# Adafruit_PiTFT_3_2in.net
KiCad netlist of a schematic drawn in EAGLE
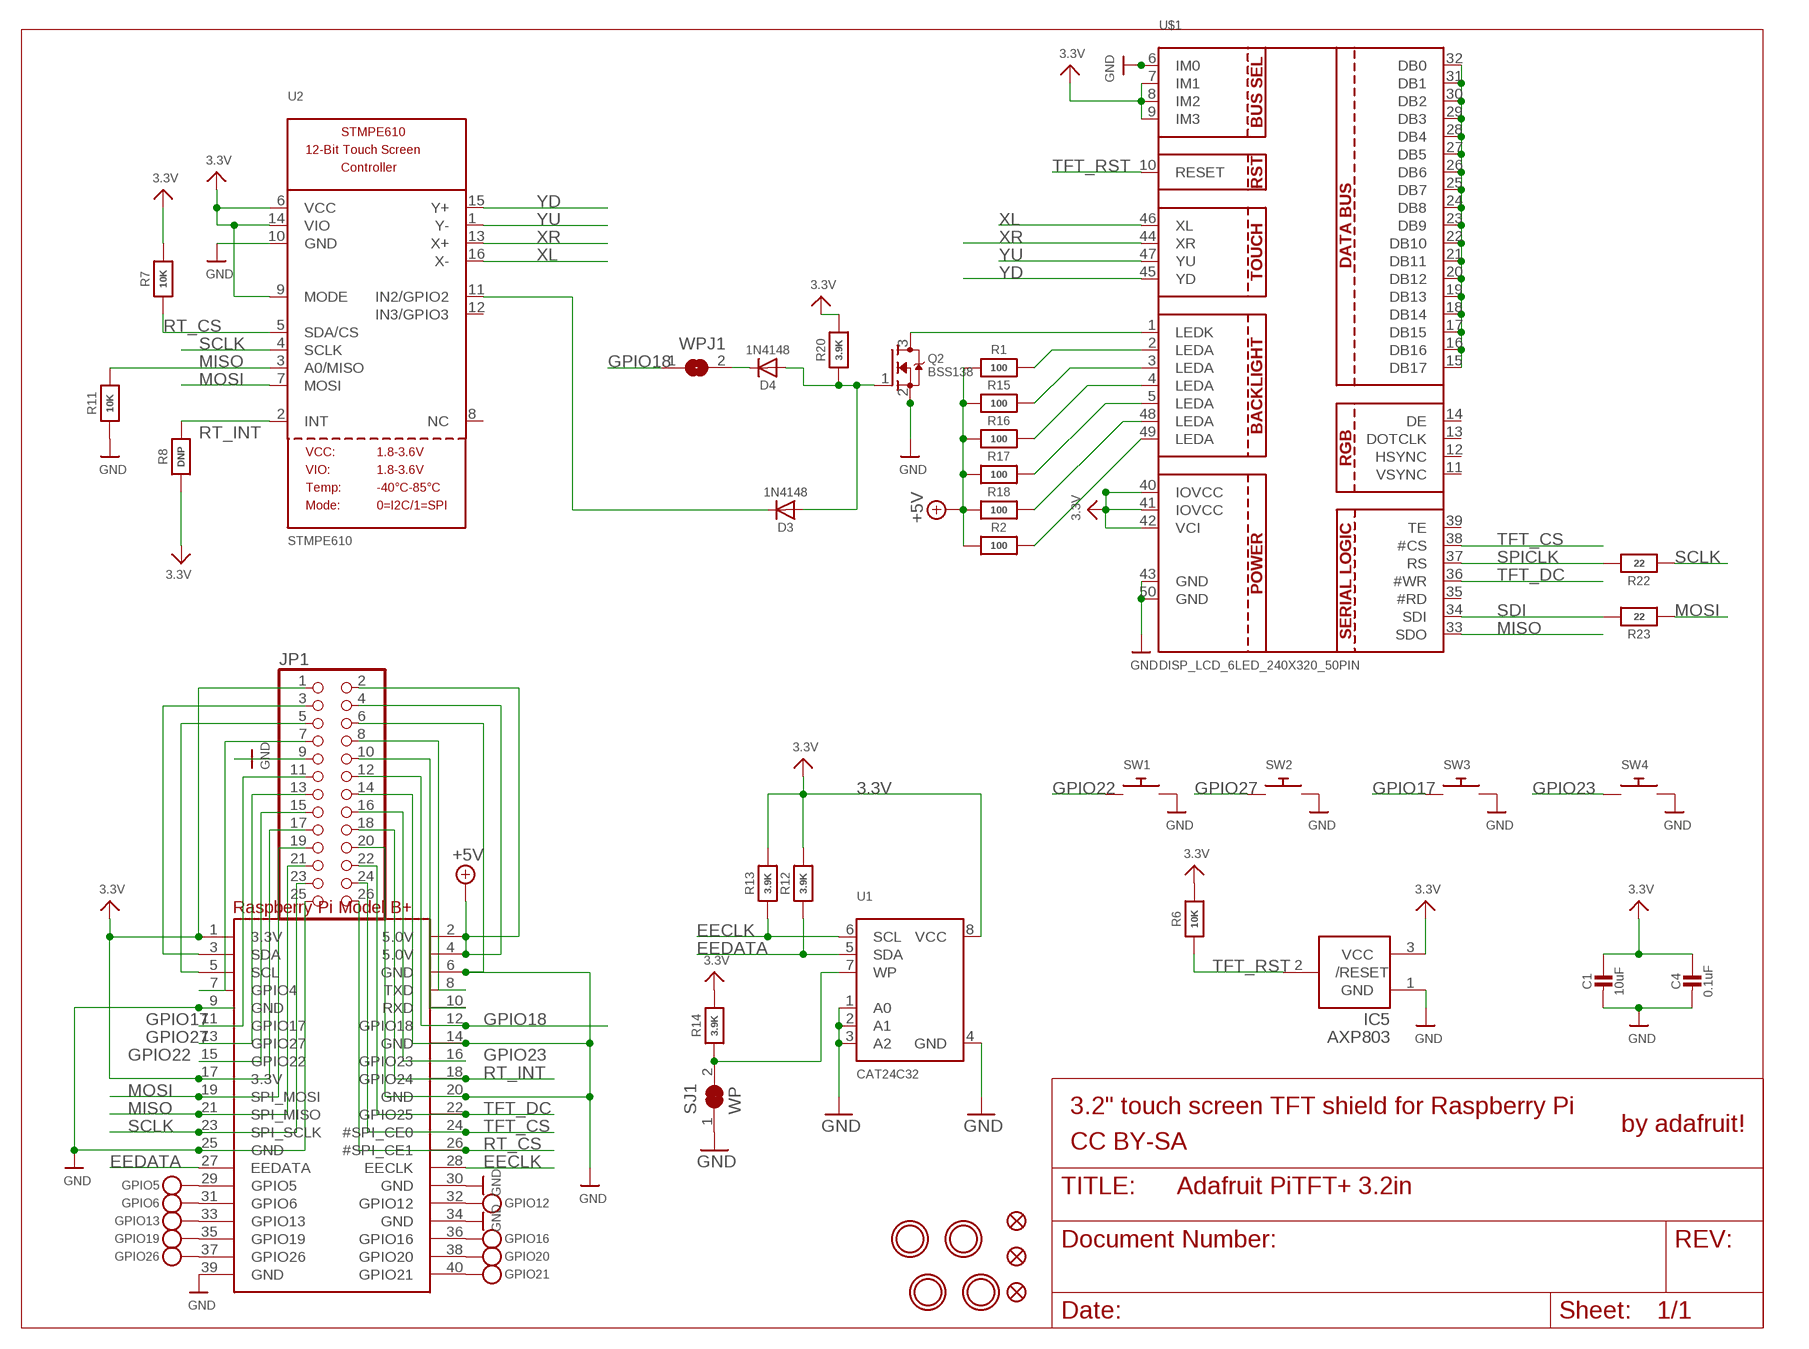
[diagram p0: schematic, sheet 1]

(export (version "E")
  (design (tool "Eeschema 10.0.6"))
  (components
    (comp (ref "C1")
      (value "10uF")
      (footprint "eagle-import:0805-NO")
      (libsource (lib "eagle-import") (part "CAP_CERAMIC0805-NOOUTLINE"))
    )
    (comp (ref "C4")
      (value "0.1uF")
      (footprint "eagle-import:0805-NO")
      (libsource (lib "eagle-import") (part "CAP_CERAMIC0805-NOOUTLINE"))
    )
    (comp (ref "D3")
      (value "1N4148")
      (footprint "eagle-import:SOD-323")
      (libsource (lib "eagle-import") (part "DIODESOD-323"))
    )
    (comp (ref "D4")
      (value "1N4148")
      (footprint "eagle-import:SOD-323")
      (libsource (lib "eagle-import") (part "DIODESOD-323"))
    )
    (comp (ref "GPIO5")
      (value "TESTPOINT1.5X2.0MM_NOCREAM")
      (footprint "eagle-import:PAD-1.5X2.0")
      (libsource (lib "eagle-import") (part "TESTPOINT1.5X2.0MM_NOCREAM"))
    )
    (comp (ref "GPIO6")
      (value "TESTPOINT1.5X2.0MM_NOCREAM")
      (footprint "eagle-import:PAD-1.5X2.0")
      (libsource (lib "eagle-import") (part "TESTPOINT1.5X2.0MM_NOCREAM"))
    )
    (comp (ref "GPIO12")
      (value "TESTPOINT1.5X2.0MM_NOCREAM")
      (footprint "eagle-import:PAD-1.5X2.0")
      (libsource (lib "eagle-import") (part "TESTPOINT1.5X2.0MM_NOCREAM"))
    )
    (comp (ref "GPIO13")
      (value "TESTPOINT1.5X2.0MM_NOCREAM")
      (footprint "eagle-import:PAD-1.5X2.0")
      (libsource (lib "eagle-import") (part "TESTPOINT1.5X2.0MM_NOCREAM"))
    )
    (comp (ref "GPIO16")
      (value "TESTPOINT1.5X2.0MM_NOCREAM")
      (footprint "eagle-import:PAD-1.5X2.0")
      (libsource (lib "eagle-import") (part "TESTPOINT1.5X2.0MM_NOCREAM"))
    )
    (comp (ref "GPIO19")
      (value "TESTPOINT1.5X2.0MM_NOCREAM")
      (footprint "eagle-import:PAD-1.5X2.0")
      (libsource (lib "eagle-import") (part "TESTPOINT1.5X2.0MM_NOCREAM"))
    )
    (comp (ref "GPIO20")
      (value "TESTPOINT1.5X2.0MM_NOCREAM")
      (footprint "eagle-import:PAD-1.5X2.0")
      (libsource (lib "eagle-import") (part "TESTPOINT1.5X2.0MM_NOCREAM"))
    )
    (comp (ref "GPIO21")
      (value "TESTPOINT1.5X2.0MM_NOCREAM")
      (footprint "eagle-import:PAD-1.5X2.0")
      (libsource (lib "eagle-import") (part "TESTPOINT1.5X2.0MM_NOCREAM"))
    )
    (comp (ref "GPIO26")
      (value "TESTPOINT1.5X2.0MM_NOCREAM")
      (footprint "eagle-import:PAD-1.5X2.0")
      (libsource (lib "eagle-import") (part "TESTPOINT1.5X2.0MM_NOCREAM"))
    )
    (comp (ref "IC5")
      (value "AXP803")
      (footprint "eagle-import:SOT23")
      (libsource (lib "eagle-import") (part "AXP083-SAG"))
    )
    (comp (ref "JP1")
      (value "HEADER-2X13-SMT")
      (footprint "eagle-import:2X13_SMT_MALE")
      (libsource (lib "eagle-import") (part "HEADER-2X13-SMT"))
    )
    (comp (ref "Q2")
      (value "BSS138")
      (footprint "eagle-import:SOT23-WIDE")
      (libsource (lib "eagle-import") (part "MOSFET-NWIDE"))
    )
    (comp (ref "R1")
      (value "100")
      (footprint "eagle-import:0805-NO")
      (libsource (lib "eagle-import") (part "RESISTOR0805_NOOUTLINE"))
    )
    (comp (ref "R2")
      (value "100")
      (footprint "eagle-import:0805-NO")
      (libsource (lib "eagle-import") (part "RESISTOR0805_NOOUTLINE"))
    )
    (comp (ref "R6")
      (value "10K")
      (footprint "eagle-import:0805-NO")
      (libsource (lib "eagle-import") (part "RESISTOR0805_NOOUTLINE"))
    )
    (comp (ref "R7")
      (value "10K")
      (footprint "eagle-import:0805-NO")
      (libsource (lib "eagle-import") (part "RESISTOR0805_NOOUTLINE"))
    )
    (comp (ref "R8")
      (value "DNP")
      (footprint "eagle-import:0805-NO")
      (libsource (lib "eagle-import") (part "RESISTOR0805_NOOUTLINE"))
    )
    (comp (ref "R11")
      (value "10K")
      (footprint "eagle-import:0805-NO")
      (libsource (lib "eagle-import") (part "RESISTOR0805_NOOUTLINE"))
    )
    (comp (ref "R12")
      (value "3.9K")
      (footprint "eagle-import:0805-NO")
      (libsource (lib "eagle-import") (part "RESISTOR0805_NOOUTLINE"))
    )
    (comp (ref "R13")
      (value "3.9K")
      (footprint "eagle-import:0805-NO")
      (libsource (lib "eagle-import") (part "RESISTOR0805_NOOUTLINE"))
    )
    (comp (ref "R14")
      (value "3.9K")
      (footprint "eagle-import:0805-NO")
      (libsource (lib "eagle-import") (part "RESISTOR0805_NOOUTLINE"))
    )
    (comp (ref "R15")
      (value "100")
      (footprint "eagle-import:0805-NO")
      (libsource (lib "eagle-import") (part "RESISTOR0805_NOOUTLINE"))
    )
    (comp (ref "R16")
      (value "100")
      (footprint "eagle-import:0805-NO")
      (libsource (lib "eagle-import") (part "RESISTOR0805_NOOUTLINE"))
    )
    (comp (ref "R17")
      (value "100")
      (footprint "eagle-import:0805-NO")
      (libsource (lib "eagle-import") (part "RESISTOR0805_NOOUTLINE"))
    )
    (comp (ref "R18")
      (value "100")
      (footprint "eagle-import:0805-NO")
      (libsource (lib "eagle-import") (part "RESISTOR0805_NOOUTLINE"))
    )
    (comp (ref "R20")
      (value "3.9K")
      (footprint "eagle-import:0805-NO")
      (libsource (lib "eagle-import") (part "RESISTOR0805_NOOUTLINE"))
    )
    (comp (ref "R22")
      (value "22")
      (footprint "eagle-import:0805-NO")
      (libsource (lib "eagle-import") (part "RESISTOR0805_NOOUTLINE"))
    )
    (comp (ref "R23")
      (value "22")
      (footprint "eagle-import:_0805MP")
      (libsource (lib "eagle-import") (part "RESISTOR_0805MP"))
    )
    (comp (ref "RPI1")
      (value "RASPBERRYPI_BPLUS_SMT")
      (footprint "eagle-import:RASPBERRYPI_BPLUS_SHIELD_SMT")
      (libsource (lib "eagle-import") (part "RASPBERRYPI_BPLUS_SMT"))
    )
    (comp (ref "SJ1")
      (value "WP")
      (footprint "eagle-import:SOLDERJUMPER_CLOSEDWIRE")
      (libsource (lib "eagle-import") (part "SOLDERJUMPER_CLOSED"))
    )
    (comp (ref "SW1")
      (value "SWITCH_PUSHBUTTONEVQ-PE")
      (footprint "eagle-import:TACT_PANA-EVQ")
      (libsource (lib "eagle-import") (part "SWITCH_PUSHBUTTONEVQ-PE"))
    )
    (comp (ref "SW2")
      (value "SWITCH_PUSHBUTTONEVQ-PE")
      (footprint "eagle-import:TACT_PANA-EVQ")
      (libsource (lib "eagle-import") (part "SWITCH_PUSHBUTTONEVQ-PE"))
    )
    (comp (ref "SW3")
      (value "SWITCH_PUSHBUTTONEVQ-PE")
      (footprint "eagle-import:TACT_PANA-EVQ")
      (libsource (lib "eagle-import") (part "SWITCH_PUSHBUTTONEVQ-PE"))
    )
    (comp (ref "SW4")
      (value "SWITCH_PUSHBUTTONEVQ-PE")
      (footprint "eagle-import:TACT_PANA-EVQ")
      (libsource (lib "eagle-import") (part "SWITCH_PUSHBUTTONEVQ-PE"))
    )
    (comp (ref "U$1")
      (value "DISP_LCD_6LED_240X320_50PIN")
      (footprint "eagle-import:TFT_3.2IN_240X320_50PIN")
      (libsource (lib "eagle-import") (part "DISP_LCD_6LED_240X320_50PIN"))
    )
    (comp (ref "U$10")
      (value "FIDUCIAL\"\"")
      (footprint "eagle-import:FIDUCIAL_1MM")
      (libsource (lib "eagle-import") (part "FIDUCIAL{dblquote}{dblquote}"))
    )
    (comp (ref "U$11")
      (value "FIDUCIAL\"\"")
      (footprint "eagle-import:FIDUCIAL_1MM")
      (libsource (lib "eagle-import") (part "FIDUCIAL{dblquote}{dblquote}"))
    )
    (comp (ref "U$15")
      (value "MOUNTINGHOLE2.5_THICK")
      (footprint "eagle-import:MOUNTINGHOLE_2.5_PLATED_THICK")
      (libsource (lib "eagle-import") (part "MOUNTINGHOLE2.5_THICK"))
    )
    (comp (ref "U$16")
      (value "MOUNTINGHOLE2.5_THICK")
      (footprint "eagle-import:MOUNTINGHOLE_2.5_PLATED_THICK")
      (libsource (lib "eagle-import") (part "MOUNTINGHOLE2.5_THICK"))
    )
    (comp (ref "U$17")
      (value "MOUNTINGHOLE2.5_THICK")
      (footprint "eagle-import:MOUNTINGHOLE_2.5_PLATED_THICK")
      (fields (field (name "BOM") "EXCLUDE"))
      (libsource (lib "eagle-import") (part "MOUNTINGHOLE2.5_THICK"))
    )
    (comp (ref "U$18")
      (value "FIDUCIAL\"\"")
      (footprint "eagle-import:FIDUCIAL_1MM")
      (libsource (lib "eagle-import") (part "FIDUCIAL{dblquote}{dblquote}"))
    )
    (comp (ref "U$20")
      (value "MOUNTINGHOLE2.5_THICK")
      (footprint "eagle-import:MOUNTINGHOLE_2.5_PLATED_THICK")
      (fields (field (name "BOM") "EXCLUDE"))
      (libsource (lib "eagle-import") (part "MOUNTINGHOLE2.5_THICK"))
    )
    (comp (ref "U1")
      (value "CAT24C32")
      (footprint "eagle-import:SOIC8_150MIL")
      (libsource (lib "eagle-import") (part "EEPROM_I2C_SOIC8_GENERIC"))
    )
    (comp (ref "U2")
      (value "STMPE610")
      (footprint "eagle-import:QFN16_3MM")
      (libsource (lib "eagle-import") (part "STMPE610"))
    )
    (comp (ref "WPJ1")
      (value "SOLDERJUMPERCLOSED")
      (footprint "eagle-import:SOLDERJUMPER_CLOSEDWIRE")
      (libsource (lib "eagle-import") (part "SOLDERJUMPERCLOSED"))
    )
  )
  (nets
    (net (code "1") (name "+5V") (class "Default")
      (node (ref "JP1") (pin "2") (pinfunction "2_2") (pintype "passive"))
      (node (ref "JP1") (pin "4") (pinfunction "4_4") (pintype "passive"))
      (node (ref "R1") (pin "1") (pinfunction "1_1") (pintype "passive"))
      (node (ref "R15") (pin "1") (pinfunction "1_1") (pintype "passive"))
      (node (ref "R16") (pin "1") (pinfunction "1_1") (pintype "passive"))
      (node (ref "R17") (pin "1") (pinfunction "1_1") (pintype "passive"))
      (node (ref "R18") (pin "1") (pinfunction "1_1") (pintype "passive"))
      (node (ref "R2") (pin "1") (pinfunction "1_1") (pintype "passive"))
      (node (ref "RPI1") (pin "2") (pinfunction "5.0V_2") (pintype "power_in"))
      (node (ref "RPI1") (pin "4") (pinfunction "5.0V_4") (pintype "power_in"))
    )
    (net (code "2") (name "/EECLK") (class "Default")
      (node (ref "R13") (pin "1") (pinfunction "1_1") (pintype "passive"))
      (node (ref "RPI1") (pin "28") (pinfunction "EECLK_28") (pintype "bidirectional"))
      (node (ref "U1") (pin "6") (pinfunction "SCL_6") (pintype "input"))
    )
    (net (code "3") (name "/EEDATA") (class "Default")
      (node (ref "R12") (pin "1") (pinfunction "1_1") (pintype "passive"))
      (node (ref "RPI1") (pin "27") (pinfunction "EEDATA_27") (pintype "bidirectional"))
      (node (ref "U1") (pin "5") (pinfunction "SDA_5") (pintype "bidirectional"))
    )
    (net (code "4") (name "/GPIO17") (class "Default")
      (node (ref "JP1") (pin "11") (pinfunction "11_11") (pintype "passive"))
      (node (ref "RPI1") (pin "11") (pinfunction "GPIO17_11") (pintype "bidirectional"))
      (node (ref "SW3") (pin "P$1") (pinfunction "P$1_P$1") (pintype "passive"))
    )
    (net (code "5") (name "/GPIO18") (class "Default")
      (node (ref "JP1") (pin "12") (pinfunction "12_12") (pintype "passive"))
      (node (ref "RPI1") (pin "12") (pinfunction "GPIO18_12") (pintype "bidirectional"))
      (node (ref "WPJ1") (pin "1") (pinfunction "1_1") (pintype "passive"))
    )
    (net (code "6") (name "/GPIO22") (class "Default")
      (node (ref "JP1") (pin "15") (pinfunction "15_15") (pintype "passive"))
      (node (ref "RPI1") (pin "15") (pinfunction "GPIO22_15") (pintype "bidirectional"))
      (node (ref "SW1") (pin "P$1") (pinfunction "P$1_P$1") (pintype "passive"))
    )
    (net (code "7") (name "/GPIO23") (class "Default")
      (node (ref "JP1") (pin "16") (pinfunction "16_16") (pintype "passive"))
      (node (ref "RPI1") (pin "16") (pinfunction "GPIO23_16") (pintype "bidirectional"))
      (node (ref "SW4") (pin "P$1") (pinfunction "P$1_P$1") (pintype "passive"))
    )
    (net (code "8") (name "/GPIO27") (class "Default")
      (node (ref "JP1") (pin "13") (pinfunction "13_13") (pintype "passive"))
      (node (ref "RPI1") (pin "13") (pinfunction "GPIO27_13") (pintype "bidirectional"))
      (node (ref "SW2") (pin "P$1") (pinfunction "P$1_P$1") (pintype "passive"))
    )
    (net (code "9") (name "/MISO") (class "Default")
      (node (ref "JP1") (pin "21") (pinfunction "21_21") (pintype "passive"))
      (node (ref "R11") (pin "2") (pinfunction "2_2") (pintype "passive"))
      (node (ref "RPI1") (pin "21") (pinfunction "SPI_MISO_21") (pintype "bidirectional"))
      (node (ref "U$1") (pin "33") (pinfunction "SDO_33") (pintype "bidirectional"))
      (node (ref "U2") (pin "3") (pinfunction "A0/MISO_3") (pintype "bidirectional"))
    )
    (net (code "10") (name "/MOSI") (class "Default")
      (node (ref "JP1") (pin "19") (pinfunction "19_19") (pintype "passive"))
      (node (ref "R23") (pin "1") (pinfunction "1_1") (pintype "passive"))
      (node (ref "RPI1") (pin "19") (pinfunction "SPI_MOSI_19") (pintype "bidirectional"))
      (node (ref "U2") (pin "7") (pinfunction "MOSI_7") (pintype "input"))
    )
    (net (code "11") (name "/RT_CS") (class "Default")
      (node (ref "JP1") (pin "26") (pinfunction "26_26") (pintype "passive"))
      (node (ref "R7") (pin "1") (pinfunction "1_1") (pintype "passive"))
      (node (ref "RPI1") (pin "26") (pinfunction "#SPI_CE1_26") (pintype "bidirectional"))
      (node (ref "U2") (pin "5") (pinfunction "SDA/CS_5") (pintype "bidirectional"))
    )
    (net (code "12") (name "/RT_INT") (class "Default")
      (node (ref "JP1") (pin "18") (pinfunction "18_18") (pintype "passive"))
      (node (ref "R8") (pin "2") (pinfunction "2_2") (pintype "passive"))
      (node (ref "RPI1") (pin "18") (pinfunction "GPIO24_18") (pintype "bidirectional"))
      (node (ref "U2") (pin "2") (pinfunction "INT_2") (pintype "output"))
    )
    (net (code "13") (name "/SCLK") (class "Default")
      (node (ref "JP1") (pin "23") (pinfunction "23_23") (pintype "passive"))
      (node (ref "R22") (pin "1") (pinfunction "1_1") (pintype "passive"))
      (node (ref "RPI1") (pin "23") (pinfunction "SPI_SCLK_23") (pintype "bidirectional"))
      (node (ref "U2") (pin "4") (pinfunction "SCLK_4") (pintype "bidirectional"))
    )
    (net (code "14") (name "/SDI") (class "Default")
      (node (ref "R23") (pin "2") (pinfunction "2_2") (pintype "passive"))
      (node (ref "U$1") (pin "34") (pinfunction "SDI_34") (pintype "bidirectional"))
    )
    (net (code "15") (name "/SPICLK") (class "Default")
      (node (ref "R22") (pin "2") (pinfunction "2_2") (pintype "passive"))
      (node (ref "U$1") (pin "37") (pinfunction "RS_37") (pintype "bidirectional"))
    )
    (net (code "16") (name "/TFT_CS") (class "Default")
      (node (ref "JP1") (pin "24") (pinfunction "24_24") (pintype "passive"))
      (node (ref "RPI1") (pin "24") (pinfunction "#SPI_CE0_24") (pintype "bidirectional"))
      (node (ref "U$1") (pin "38") (pinfunction "#CS_38") (pintype "bidirectional"))
    )
    (net (code "17") (name "/TFT_DC") (class "Default")
      (node (ref "JP1") (pin "22") (pinfunction "22_22") (pintype "passive"))
      (node (ref "RPI1") (pin "22") (pinfunction "GPIO25_22") (pintype "bidirectional"))
      (node (ref "U$1") (pin "36") (pinfunction "#WR_36") (pintype "bidirectional"))
    )
    (net (code "18") (name "/TFT_RST") (class "Default")
      (node (ref "IC5") (pin "2") (pinfunction "/RESET_2") (pintype "output"))
      (node (ref "R6") (pin "1") (pinfunction "1_1") (pintype "passive"))
      (node (ref "U$1") (pin "10") (pinfunction "RESET_10") (pintype "bidirectional"))
    )
    (net (code "19") (name "/XL") (class "Default")
      (node (ref "U$1") (pin "46") (pinfunction "XL_46") (pintype "bidirectional"))
      (node (ref "U2") (pin "16") (pinfunction "X-_16") (pintype "input"))
    )
    (net (code "20") (name "/XR") (class "Default")
      (node (ref "U$1") (pin "44") (pinfunction "XR_44") (pintype "bidirectional"))
      (node (ref "U2") (pin "13") (pinfunction "X+_13") (pintype "input"))
    )
    (net (code "21") (name "/YD") (class "Default")
      (node (ref "U$1") (pin "45") (pinfunction "YD_45") (pintype "bidirectional"))
      (node (ref "U2") (pin "15") (pinfunction "Y+_15") (pintype "input"))
    )
    (net (code "22") (name "/YU") (class "Default")
      (node (ref "U$1") (pin "47") (pinfunction "YU_47") (pintype "bidirectional"))
      (node (ref "U2") (pin "1") (pinfunction "Y-_1") (pintype "input"))
    )
    (net (code "23") (name "3.3V") (class "Default")
      (node (ref "C1") (pin "1") (pinfunction "1_1") (pintype "passive"))
      (node (ref "C4") (pin "1") (pinfunction "1_1") (pintype "passive"))
      (node (ref "IC5") (pin "3") (pinfunction "VCC_3") (pintype "power_in"))
      (node (ref "JP1") (pin "1") (pinfunction "1_1") (pintype "passive"))
      (node (ref "JP1") (pin "17") (pinfunction "17_17") (pintype "passive"))
      (node (ref "R12") (pin "2") (pinfunction "2_2") (pintype "passive"))
      (node (ref "R13") (pin "2") (pinfunction "2_2") (pintype "passive"))
      (node (ref "R14") (pin "2") (pinfunction "2_2") (pintype "passive"))
      (node (ref "R20") (pin "2") (pinfunction "2_2") (pintype "passive"))
      (node (ref "R6") (pin "2") (pinfunction "2_2") (pintype "passive"))
      (node (ref "R7") (pin "2") (pinfunction "2_2") (pintype "passive"))
      (node (ref "R8") (pin "1") (pinfunction "1_1") (pintype "passive"))
      (node (ref "RPI1") (pin "1") (pinfunction "3.3V_1") (pintype "power_in"))
      (node (ref "RPI1") (pin "17") (pinfunction "3.3V_17") (pintype "power_in"))
      (node (ref "U$1") (pin "40") (pinfunction "IOVCC_40") (pintype "bidirectional"))
      (node (ref "U$1") (pin "41") (pinfunction "IOVCC_41") (pintype "bidirectional"))
      (node (ref "U$1") (pin "42") (pinfunction "VCI_42") (pintype "bidirectional"))
      (node (ref "U$1") (pin "7") (pinfunction "IM1_7") (pintype "bidirectional"))
      (node (ref "U$1") (pin "8") (pinfunction "IM2_8") (pintype "bidirectional"))
      (node (ref "U$1") (pin "9") (pinfunction "IM3_9") (pintype "bidirectional"))
      (node (ref "U1") (pin "8") (pinfunction "VCC_8") (pintype "power_in"))
      (node (ref "U2") (pin "14") (pinfunction "VIO_14") (pintype "power_in"))
      (node (ref "U2") (pin "6") (pinfunction "VCC_6") (pintype "power_in"))
      (node (ref "U2") (pin "9") (pinfunction "MODE_9") (pintype "input"))
    )
    (net (code "24") (name "GND") (class "Default")
      (node (ref "C1") (pin "2") (pinfunction "2_2") (pintype "passive"))
      (node (ref "C4") (pin "2") (pinfunction "2_2") (pintype "passive"))
      (node (ref "IC5") (pin "1") (pinfunction "GND_1") (pintype "power_in"))
      (node (ref "JP1") (pin "14") (pinfunction "14_14") (pintype "passive"))
      (node (ref "JP1") (pin "20") (pinfunction "20_20") (pintype "passive"))
      (node (ref "JP1") (pin "25") (pinfunction "25_25") (pintype "passive"))
      (node (ref "JP1") (pin "6") (pinfunction "6_6") (pintype "passive"))
      (node (ref "JP1") (pin "9") (pinfunction "9_9") (pintype "passive"))
      (node (ref "Q2") (pin "2") (pinfunction "S_2") (pintype "bidirectional"))
      (node (ref "R11") (pin "1") (pinfunction "1_1") (pintype "passive"))
      (node (ref "RPI1") (pin "14") (pinfunction "GND_14") (pintype "power_in"))
      (node (ref "RPI1") (pin "20") (pinfunction "GND_20") (pintype "power_in"))
      (node (ref "RPI1") (pin "25") (pinfunction "GND_25") (pintype "power_in"))
      (node (ref "RPI1") (pin "30") (pinfunction "GND_30") (pintype "power_in"))
      (node (ref "RPI1") (pin "34") (pinfunction "GND_34") (pintype "power_in"))
      (node (ref "RPI1") (pin "39") (pinfunction "GND_39") (pintype "power_in"))
      (node (ref "RPI1") (pin "6") (pinfunction "GND_6") (pintype "power_in"))
      (node (ref "RPI1") (pin "9") (pinfunction "GND_9") (pintype "power_in"))
      (node (ref "SJ1") (pin "1") (pinfunction "1_1") (pintype "passive"))
      (node (ref "SW1") (pin "P$2") (pinfunction "P$2_P$2") (pintype "passive"))
      (node (ref "SW2") (pin "P$2") (pinfunction "P$2_P$2") (pintype "passive"))
      (node (ref "SW3") (pin "P$2") (pinfunction "P$2_P$2") (pintype "passive"))
      (node (ref "SW4") (pin "P$2") (pinfunction "P$2_P$2") (pintype "passive"))
      (node (ref "U$1") (pin "43") (pinfunction "GND_43") (pintype "bidirectional"))
      (node (ref "U$1") (pin "50") (pinfunction "GND_50") (pintype "bidirectional"))
      (node (ref "U$1") (pin "6") (pinfunction "IM0_6") (pintype "bidirectional"))
      (node (ref "U1") (pin "1") (pinfunction "A0_1") (pintype "input"))
      (node (ref "U1") (pin "2") (pinfunction "A1_2") (pintype "input"))
      (node (ref "U1") (pin "3") (pinfunction "A2_3") (pintype "input"))
      (node (ref "U1") (pin "4") (pinfunction "GND_4") (pintype "power_in"))
      (node (ref "U2") (pin "10") (pinfunction "GND_10") (pintype "power_in"))
    )
    (net (code "25") (name "Net-(D4-PadC)") (class "Default")
      (node (ref "D4") (pin "C") (pinfunction "C_C") (pintype "passive"))
      (node (ref "WPJ1") (pin "2") (pinfunction "2_2") (pintype "passive"))
    )
    (net (code "26") (name "Net-(Q2-D)") (class "Default")
      (node (ref "Q2") (pin "3") (pinfunction "D_3") (pintype "bidirectional"))
      (node (ref "U$1") (pin "1") (pinfunction "LEDK_1") (pintype "bidirectional"))
    )
    (net (code "27") (name "Net-(Q2-G)") (class "Default")
      (node (ref "D3") (pin "A") (pinfunction "A_A") (pintype "passive"))
      (node (ref "D4") (pin "A") (pinfunction "A_A") (pintype "passive"))
      (node (ref "Q2") (pin "1") (pinfunction "G_1") (pintype "bidirectional"))
      (node (ref "R20") (pin "1") (pinfunction "1_1") (pintype "passive"))
    )
    (net (code "28") (name "Net-(R1-Pad2)") (class "Default")
      (node (ref "R1") (pin "2") (pinfunction "2_2") (pintype "passive"))
      (node (ref "U$1") (pin "2") (pinfunction "LEDA_2") (pintype "bidirectional"))
    )
    (net (code "29") (name "Net-(R2-Pad2)") (class "Default")
      (node (ref "R2") (pin "2") (pinfunction "2_2") (pintype "passive"))
      (node (ref "U$1") (pin "49") (pinfunction "LEDA_49") (pintype "bidirectional"))
    )
    (net (code "30") (name "Net-(R15-Pad2)") (class "Default")
      (node (ref "R15") (pin "2") (pinfunction "2_2") (pintype "passive"))
      (node (ref "U$1") (pin "3") (pinfunction "LEDA_3") (pintype "bidirectional"))
    )
    (net (code "31") (name "Net-(R16-Pad2)") (class "Default")
      (node (ref "R16") (pin "2") (pinfunction "2_2") (pintype "passive"))
      (node (ref "U$1") (pin "4") (pinfunction "LEDA_4") (pintype "bidirectional"))
    )
    (net (code "32") (name "Net-(R17-Pad2)") (class "Default")
      (node (ref "R17") (pin "2") (pinfunction "2_2") (pintype "passive"))
      (node (ref "U$1") (pin "5") (pinfunction "LEDA_5") (pintype "bidirectional"))
    )
    (net (code "33") (name "Net-(R18-Pad2)") (class "Default")
      (node (ref "R18") (pin "2") (pinfunction "2_2") (pintype "passive"))
      (node (ref "U$1") (pin "48") (pinfunction "LEDA_48") (pintype "bidirectional"))
    )
    (net (code "34") (name "Net-(RPI1-GPIO4)") (class "Default")
      (node (ref "JP1") (pin "7") (pinfunction "7_7") (pintype "passive"))
      (node (ref "RPI1") (pin "7") (pinfunction "GPIO4_7") (pintype "bidirectional"))
    )
    (net (code "35") (name "Net-(RPI1-GPIO5)") (class "Default")
      (node (ref "GPIO5") (pin "P$1") (pinfunction "P$1_P$1") (pintype "bidirectional"))
      (node (ref "RPI1") (pin "29") (pinfunction "GPIO5_29") (pintype "bidirectional"))
    )
    (net (code "36") (name "Net-(RPI1-GPIO6)") (class "Default")
      (node (ref "GPIO6") (pin "P$1") (pinfunction "P$1_P$1") (pintype "bidirectional"))
      (node (ref "RPI1") (pin "31") (pinfunction "GPIO6_31") (pintype "bidirectional"))
    )
    (net (code "37") (name "Net-(RPI1-GPIO12)") (class "Default")
      (node (ref "GPIO12") (pin "P$1") (pinfunction "P$1_P$1") (pintype "bidirectional"))
      (node (ref "RPI1") (pin "32") (pinfunction "GPIO12_32") (pintype "bidirectional"))
    )
    (net (code "38") (name "Net-(RPI1-GPIO13)") (class "Default")
      (node (ref "GPIO13") (pin "P$1") (pinfunction "P$1_P$1") (pintype "bidirectional"))
      (node (ref "RPI1") (pin "33") (pinfunction "GPIO13_33") (pintype "bidirectional"))
    )
    (net (code "39") (name "Net-(RPI1-GPIO16)") (class "Default")
      (node (ref "GPIO16") (pin "P$1") (pinfunction "P$1_P$1") (pintype "bidirectional"))
      (node (ref "RPI1") (pin "36") (pinfunction "GPIO16_36") (pintype "bidirectional"))
    )
    (net (code "40") (name "Net-(RPI1-GPIO19)") (class "Default")
      (node (ref "GPIO19") (pin "P$1") (pinfunction "P$1_P$1") (pintype "bidirectional"))
      (node (ref "RPI1") (pin "35") (pinfunction "GPIO19_35") (pintype "bidirectional"))
    )
    (net (code "41") (name "Net-(RPI1-GPIO20)") (class "Default")
      (node (ref "GPIO20") (pin "P$1") (pinfunction "P$1_P$1") (pintype "bidirectional"))
      (node (ref "RPI1") (pin "38") (pinfunction "GPIO20_38") (pintype "bidirectional"))
    )
    (net (code "42") (name "Net-(RPI1-GPIO21)") (class "Default")
      (node (ref "GPIO21") (pin "P$1") (pinfunction "P$1_P$1") (pintype "bidirectional"))
      (node (ref "RPI1") (pin "40") (pinfunction "GPIO21_40") (pintype "bidirectional"))
    )
    (net (code "43") (name "Net-(RPI1-GPIO26)") (class "Default")
      (node (ref "GPIO26") (pin "P$1") (pinfunction "P$1_P$1") (pintype "bidirectional"))
      (node (ref "RPI1") (pin "37") (pinfunction "GPIO26_37") (pintype "bidirectional"))
    )
    (net (code "44") (name "Net-(RPI1-RXD)") (class "Default")
      (node (ref "JP1") (pin "10") (pinfunction "10_10") (pintype "passive"))
      (node (ref "RPI1") (pin "10") (pinfunction "RXD_10") (pintype "bidirectional"))
    )
    (net (code "45") (name "Net-(RPI1-SCL)") (class "Default")
      (node (ref "JP1") (pin "5") (pinfunction "5_5") (pintype "passive"))
      (node (ref "RPI1") (pin "5") (pinfunction "SCL_5") (pintype "bidirectional"))
    )
    (net (code "46") (name "Net-(RPI1-SDA)") (class "Default")
      (node (ref "JP1") (pin "3") (pinfunction "3_3") (pintype "passive"))
      (node (ref "RPI1") (pin "3") (pinfunction "SDA_3") (pintype "bidirectional"))
    )
    (net (code "47") (name "Net-(RPI1-TXD)") (class "Default")
      (node (ref "JP1") (pin "8") (pinfunction "8_8") (pintype "passive"))
      (node (ref "RPI1") (pin "8") (pinfunction "TXD_8") (pintype "bidirectional"))
    )
    (net (code "48") (name "Net-(U$1-DB0)") (class "Default")
      (node (ref "U$1") (pin "15") (pinfunction "DB17_15") (pintype "bidirectional"))
      (node (ref "U$1") (pin "16") (pinfunction "DB16_16") (pintype "bidirectional"))
      (node (ref "U$1") (pin "17") (pinfunction "DB15_17") (pintype "bidirectional"))
      (node (ref "U$1") (pin "18") (pinfunction "DB14_18") (pintype "bidirectional"))
      (node (ref "U$1") (pin "19") (pinfunction "DB13_19") (pintype "bidirectional"))
      (node (ref "U$1") (pin "20") (pinfunction "DB12_20") (pintype "bidirectional"))
      (node (ref "U$1") (pin "21") (pinfunction "DB11_21") (pintype "bidirectional"))
      (node (ref "U$1") (pin "22") (pinfunction "DB10_22") (pintype "bidirectional"))
      (node (ref "U$1") (pin "23") (pinfunction "DB9_23") (pintype "bidirectional"))
      (node (ref "U$1") (pin "24") (pinfunction "DB8_24") (pintype "bidirectional"))
      (node (ref "U$1") (pin "25") (pinfunction "DB7_25") (pintype "bidirectional"))
      (node (ref "U$1") (pin "26") (pinfunction "DB6_26") (pintype "bidirectional"))
      (node (ref "U$1") (pin "27") (pinfunction "DB5_27") (pintype "bidirectional"))
      (node (ref "U$1") (pin "28") (pinfunction "DB4_28") (pintype "bidirectional"))
      (node (ref "U$1") (pin "29") (pinfunction "DB3_29") (pintype "bidirectional"))
      (node (ref "U$1") (pin "30") (pinfunction "DB2_30") (pintype "bidirectional"))
      (node (ref "U$1") (pin "31") (pinfunction "DB1_31") (pintype "bidirectional"))
      (node (ref "U$1") (pin "32") (pinfunction "DB0_32") (pintype "bidirectional"))
    )
    (net (code "49") (name "Net-(U1-WP)") (class "Default")
      (node (ref "R14") (pin "1") (pinfunction "1_1") (pintype "passive"))
      (node (ref "SJ1") (pin "2") (pinfunction "2_2") (pintype "passive"))
      (node (ref "U1") (pin "7") (pinfunction "WP_7") (pintype "input"))
    )
    (net (code "50") (name "Net-(U2-IN2{slash}GPIO2)") (class "Default")
      (node (ref "D3") (pin "C") (pinfunction "C_C") (pintype "passive"))
      (node (ref "U2") (pin "11") (pinfunction "IN2/GPIO2_11") (pintype "bidirectional"))
    )
    (net (code "51") (name "unconnected-(U$1-#RD-Pad35)") (class "Default")
      (node (ref "U$1") (pin "35") (pinfunction "#RD_35") (pintype "bidirectional"))
    )
    (net (code "52") (name "unconnected-(U$1-DE-Pad14)") (class "Default")
      (node (ref "U$1") (pin "14") (pinfunction "DE_14") (pintype "bidirectional"))
    )
    (net (code "53") (name "unconnected-(U$1-DOTCLK-Pad13)") (class "Default")
      (node (ref "U$1") (pin "13") (pinfunction "DOTCLK_13") (pintype "bidirectional"))
    )
    (net (code "54") (name "unconnected-(U$1-HSYNC-Pad12)") (class "Default")
      (node (ref "U$1") (pin "12") (pinfunction "HSYNC_12") (pintype "bidirectional"))
    )
    (net (code "55") (name "unconnected-(U$1-TE-Pad39)") (class "Default")
      (node (ref "U$1") (pin "39") (pinfunction "TE_39") (pintype "bidirectional"))
    )
    (net (code "56") (name "unconnected-(U$1-VSYNC-Pad11)") (class "Default")
      (node (ref "U$1") (pin "11") (pinfunction "VSYNC_11") (pintype "bidirectional"))
    )
    (net (code "57") (name "unconnected-(U2-IN3{slash}GPIO3-Pad12)") (class "Default")
      (node (ref "U2") (pin "12") (pinfunction "IN3/GPIO3_12") (pintype "bidirectional"))
    )
    (net (code "58") (name "unconnected-(U2-NC-Pad8)") (class "Default")
      (node (ref "U2") (pin "8") (pinfunction "NC_8") (pintype "no_connect"))
    )
  )
)
